# tinyPCB.net
KiCad netlist of a schematic drawn in EAGLE
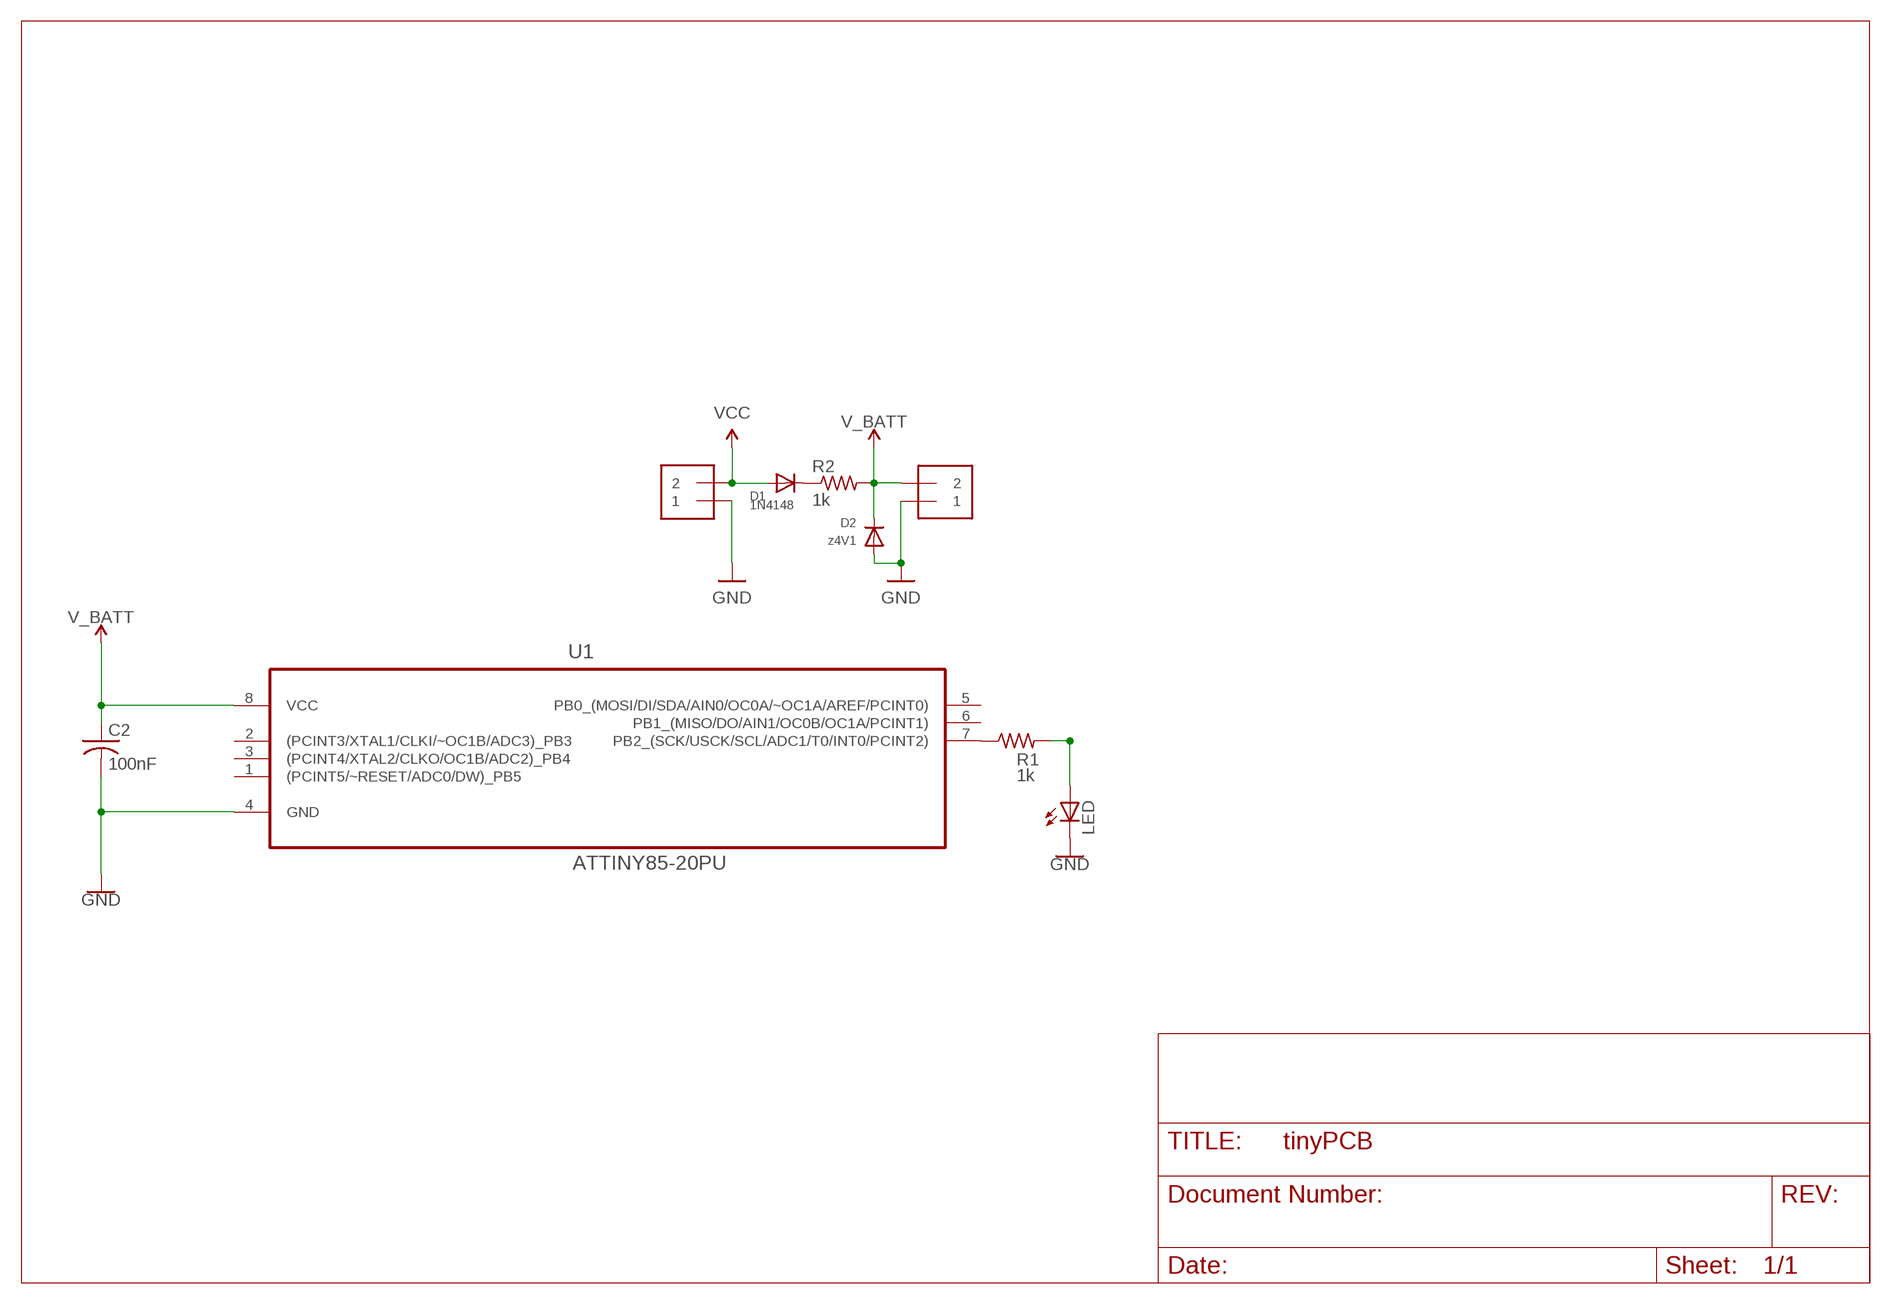
[diagram p0: schematic, sheet 1]

(export (version "E")
  (design (tool "Eeschema 10.0.6"))
  (components
    (comp (ref "BAT")
      (value "1X2-3.5MM")
      (footprint "eagle-import:1X2-3.5MM")
      (libsource (lib "eagle-import") (part "1X2-3.5MM"))
    )
    (comp (ref "C2")
      (value "100nF")
      (footprint "eagle-import:C050-025X075")
      (libsource (lib "eagle-import") (part "C-US050-025X075"))
    )
    (comp (ref "CHG")
      (value "1X2-3.5MM")
      (footprint "eagle-import:1X2-3.5MM")
      (libsource (lib "eagle-import") (part "1X2-3.5MM"))
    )
    (comp (ref "D1")
      (value "1N4148")
      (footprint "eagle-import:DO-1N4148")
      (libsource (lib "eagle-import") (part "DIODEDO-1N4148"))
    )
    (comp (ref "D2")
      (value "z4V1")
      (footprint "eagle-import:DO-1N4148")
      (libsource (lib "eagle-import") (part "DIODEDO-1N4148"))
    )
    (comp (ref "LED")
      (value "LED5MM")
      (footprint "eagle-import:LED5MM")
      (libsource (lib "eagle-import") (part "LED5MM"))
    )
    (comp (ref "R1")
      (value "1k")
      (footprint "eagle-import:0204_7")
      (libsource (lib "eagle-import") (part "R-US_0204/7"))
    )
    (comp (ref "R2")
      (value "1k")
      (footprint "eagle-import:0204_7")
      (libsource (lib "eagle-import") (part "R-US_0204/7"))
    )
    (comp (ref "U1")
      (value "ATTINY85-20PU")
      (footprint "eagle-import:DIP254P762X533-8")
      (fields (field (name "MF") "Microchip"))
      (libsource (lib "eagle-import") (part "ATTINY85-20PU"))
    )
  )
  (nets
    (net (code "1") (name "GND") (class "Default")
      (node (ref "BAT") (pin "1") (pinfunction "1_1") (pintype "passive"))
      (node (ref "C2") (pin "2") (pinfunction "2_2") (pintype "passive"))
      (node (ref "CHG") (pin "1") (pinfunction "1_1") (pintype "passive"))
      (node (ref "D2") (pin "A") (pinfunction "A_A") (pintype "passive"))
      (node (ref "LED") (pin "K") (pinfunction "C_K") (pintype "passive"))
      (node (ref "U1") (pin "4") (pinfunction "GND_4") (pintype "passive"))
    )
    (net (code "2") (name "Net-(D1-PadC)") (class "Default")
      (node (ref "D1") (pin "C") (pinfunction "C_C") (pintype "passive"))
      (node (ref "R2") (pin "1") (pinfunction "1_1") (pintype "passive"))
    )
    (net (code "3") (name "Net-(LED-PadA)") (class "Default")
      (node (ref "LED") (pin "A") (pinfunction "A_A") (pintype "passive"))
      (node (ref "R1") (pin "2") (pinfunction "2_2") (pintype "passive"))
    )
    (net (code "4") (name "Net-(U1-PB2_(SCK{slash}USCK{slash}SCL{slash}ADC1{slash}T0{slash}INT0{slash}PCINT2))") (class "Default")
      (node (ref "R1") (pin "1") (pinfunction "1_1") (pintype "passive"))
      (node (ref "U1") (pin "7") (pinfunction "PB2_(SCK/USCK/SCL/ADC1/T0/INT0/PCINT2)_7") (pintype "bidirectional"))
    )
    (net (code "5") (name "VCC") (class "Default")
      (node (ref "CHG") (pin "2") (pinfunction "2_2") (pintype "passive"))
      (node (ref "D1") (pin "A") (pinfunction "A_A") (pintype "passive"))
    )
    (net (code "6") (name "V_BATT") (class "Default")
      (node (ref "BAT") (pin "2") (pinfunction "2_2") (pintype "passive"))
      (node (ref "C2") (pin "1") (pinfunction "1_1") (pintype "passive"))
      (node (ref "D2") (pin "C") (pinfunction "C_C") (pintype "passive"))
      (node (ref "R2") (pin "2") (pinfunction "2_2") (pintype "passive"))
      (node (ref "U1") (pin "8") (pinfunction "VCC_8") (pintype "power_in"))
    )
    (net (code "7") (name "unconnected-(U1-(PCINT3{slash}XTAL1{slash}CLKI{slash}~{OC1B{slash}ADC3})_PB3-Pad2)") (class "Default")
      (node (ref "U1") (pin "2") (pinfunction "(PCINT3/XTAL1/CLKI/~{OC1B/ADC3})_PB3_2") (pintype "bidirectional"))
    )
    (net (code "8") (name "unconnected-(U1-(PCINT4{slash}XTAL2{slash}CLKO{slash}OC1B{slash}ADC2)_PB4-Pad3)") (class "Default")
      (node (ref "U1") (pin "3") (pinfunction "(PCINT4/XTAL2/CLKO/OC1B/ADC2)_PB4_3") (pintype "bidirectional"))
    )
    (net (code "9") (name "unconnected-(U1-(PCINT5{slash}~{RESET{slash}ADC0{slash}DW})_PB5-Pad1)") (class "Default")
      (node (ref "U1") (pin "1") (pinfunction "(PCINT5/~{RESET/ADC0/DW})_PB5_1") (pintype "bidirectional"))
    )
    (net (code "10") (name "unconnected-(U1-PB0_(MOSI{slash}DI{slash}SDA{slash}AIN0{slash}OC0A{slash}~{OC1A{slash}AREF{slash}PCINT0})-Pad5)") (class "Default")
      (node (ref "U1") (pin "5") (pinfunction "PB0_(MOSI/DI/SDA/AIN0/OC0A/~{OC1A/AREF/PCINT0})_5") (pintype "bidirectional"))
    )
    (net (code "11") (name "unconnected-(U1-PB1_(MISO{slash}DO{slash}AIN1{slash}OC0B{slash}OC1A{slash}PCINT1)-Pad6)") (class "Default")
      (node (ref "U1") (pin "6") (pinfunction "PB1_(MISO/DO/AIN1/OC0B/OC1A/PCINT1)_6") (pintype "bidirectional"))
    )
  )
)
